# Pratica_02.net
KiCad netlist of a schematic drawn in EasyEDA
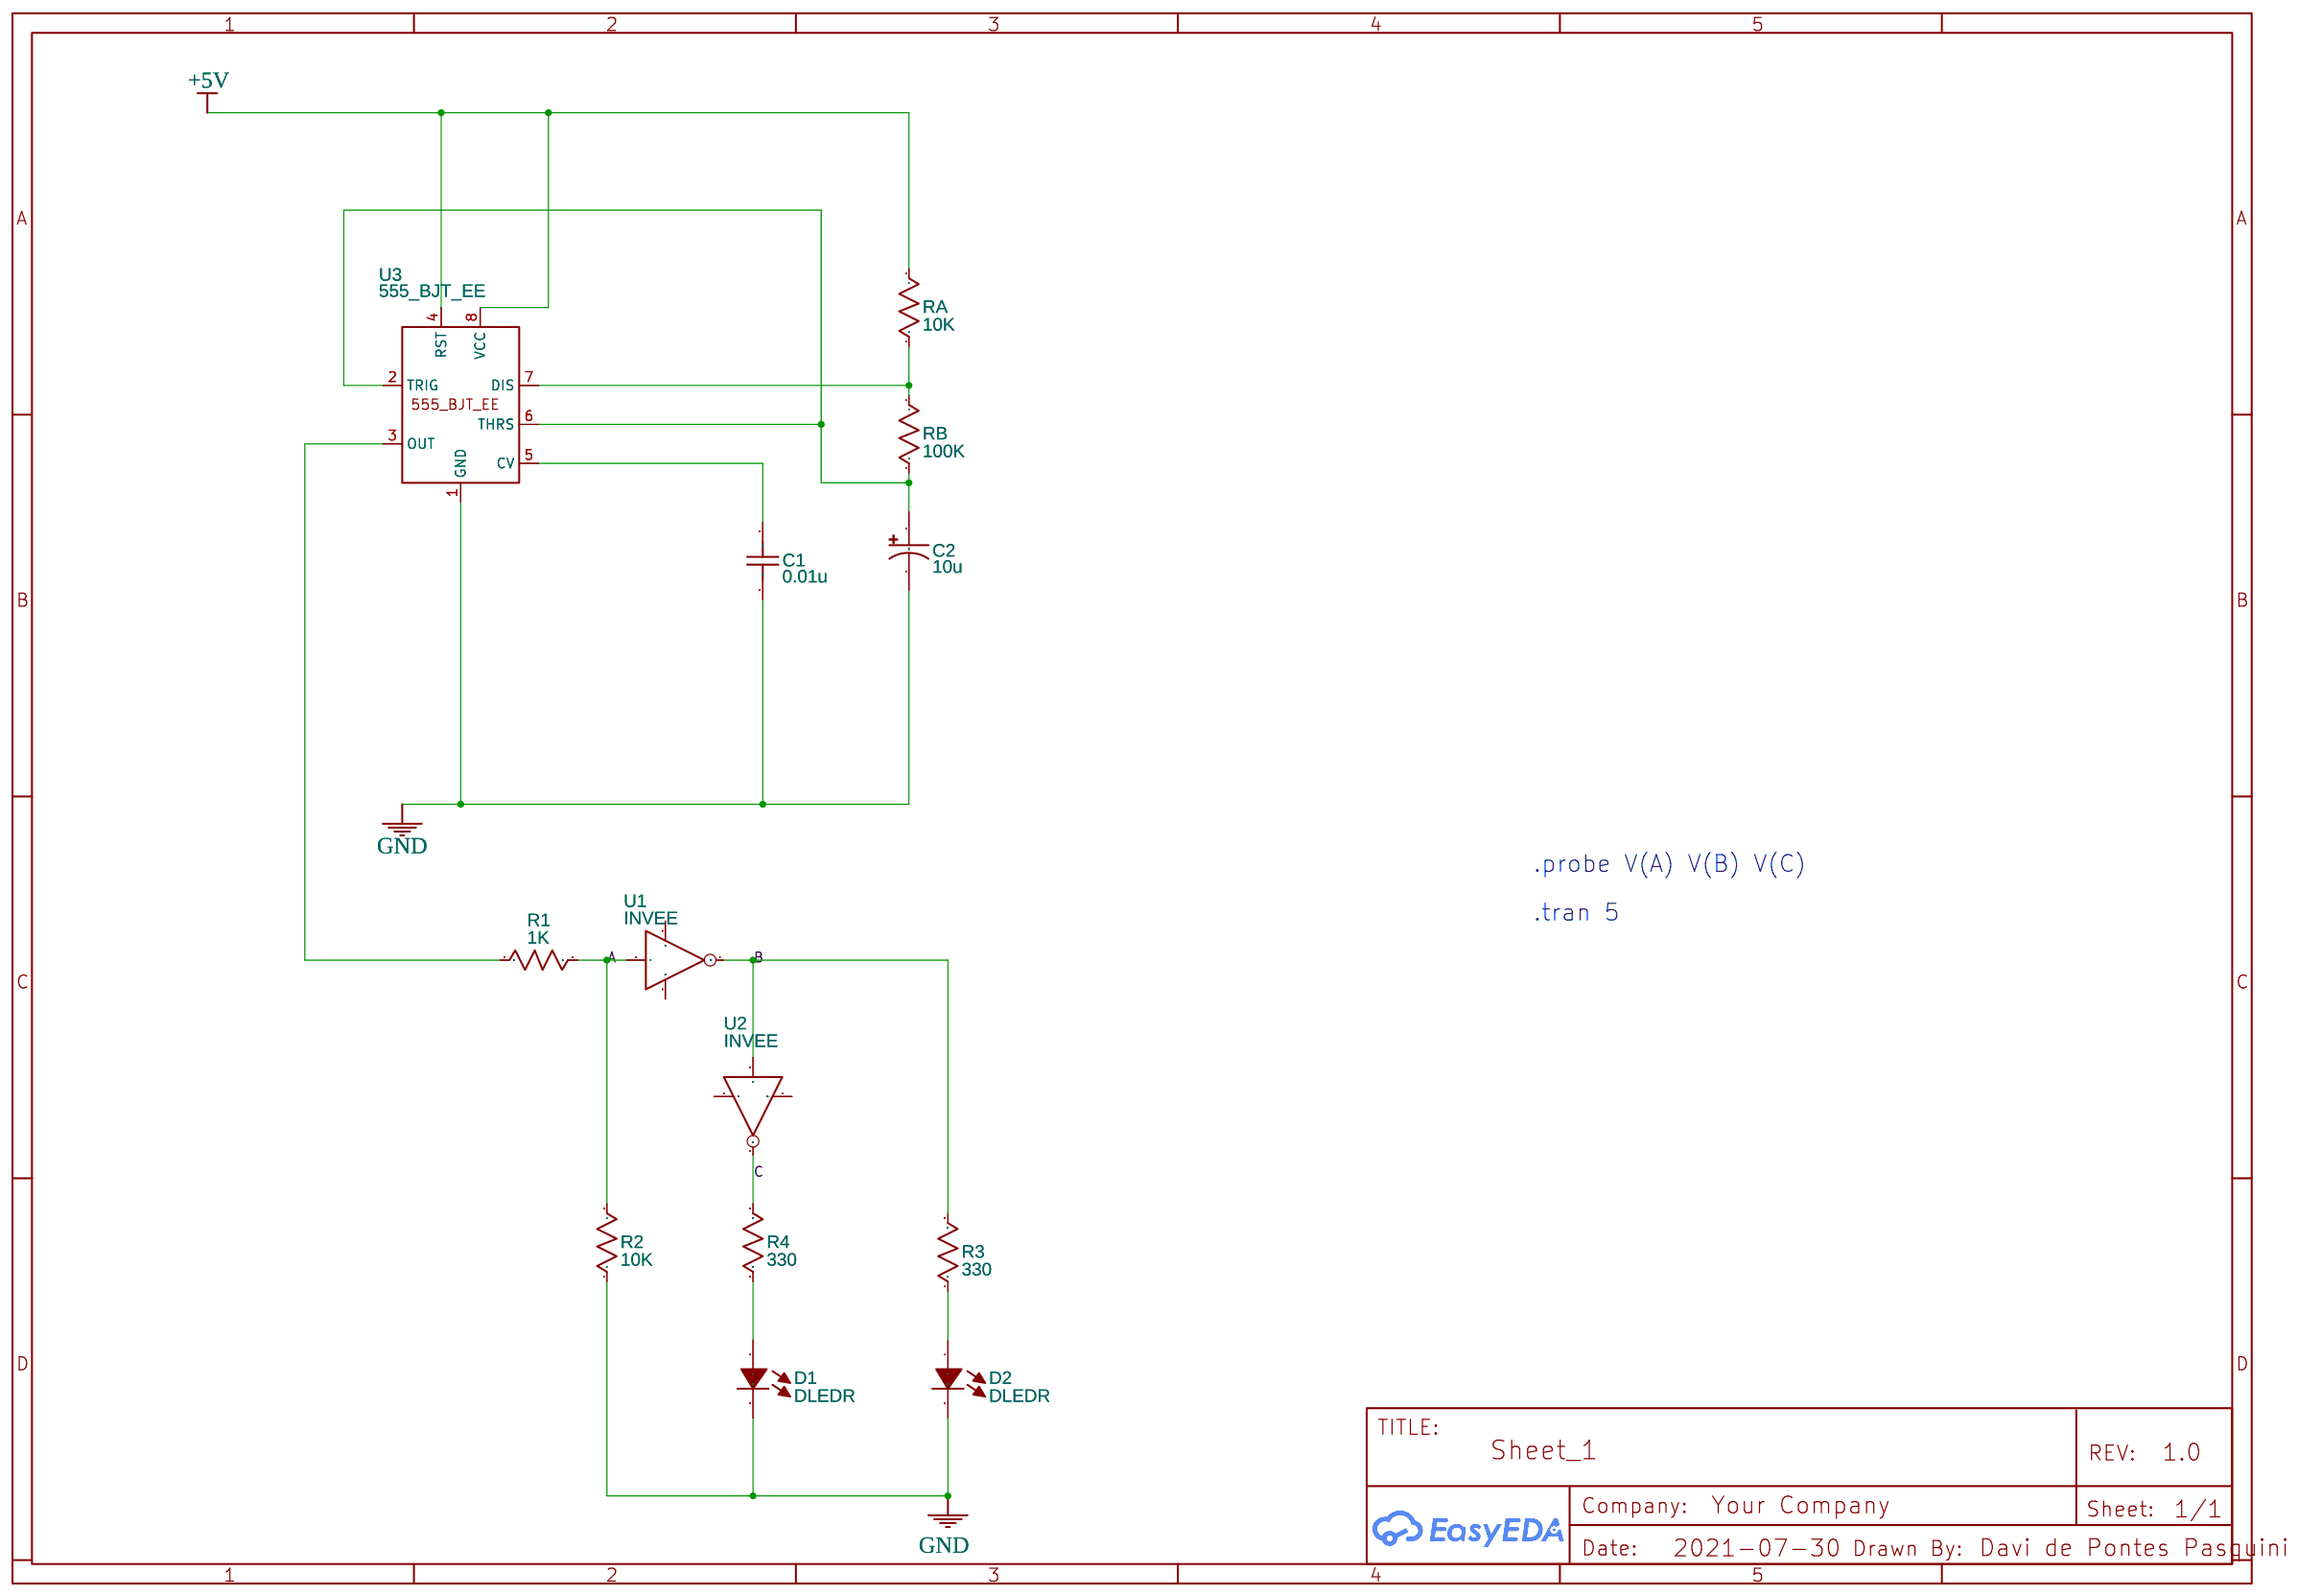
[diagram p0: schematic sheet]

(export (version "E")
  (design (tool "Eeschema 10.0.6"))
  (components
    (comp (ref "C1") (value "0.01u") (libsource (lib "") (part "Capacitor_US")))
    (comp (ref "C2") (value "10u") (libsource (lib "") (part "Capacitor_Electrolytic_US")))
    (comp (ref "D1") (value "DLEDR") (libsource (lib "") (part "DLEDR")))
    (comp (ref "D2") (value "DLEDR") (libsource (lib "") (part "DLEDR")))
    (comp (ref "R1") (value "1K") (libsource (lib "") (part "Resistor_US_1")))
    (comp (ref "R2") (value "10K") (libsource (lib "") (part "Resistor_US_2")))
    (comp (ref "R3") (value "330") (libsource (lib "") (part "Resistor_US_2")))
    (comp (ref "R4") (value "330") (libsource (lib "") (part "Resistor_US_2")))
    (comp (ref "RA") (value "10K") (libsource (lib "") (part "Resistor_US_3")))
    (comp (ref "RB") (value "100K") (libsource (lib "") (part "Resistor_US")))
    (comp (ref "U1") (value "INVEE") (libsource (lib "") (part "LOGIC")))
    (comp (ref "U2") (value "INVEE") (libsource (lib "") (part "LOGIC_1")))
    (comp (ref "U3") (value "555_BJT_EE") (libsource (lib "") (part "555_BJT_EE")))
  )
  (nets
    (net (code "1") (name "+5V") (class "Default")
      (node (ref "RA") (pin "1") (pinfunction "1_1") (pintype "unspecified"))
      (node (ref "U3") (pin "4") (pinfunction "RST_4") (pintype "unspecified"))
      (node (ref "U3") (pin "8") (pinfunction "VCC_8") (pintype "unspecified"))
    )
    (net (code "2") (name "/A") (class "Default")
      (node (ref "R1") (pin "2") (pinfunction "2_2") (pintype "unspecified"))
      (node (ref "R2") (pin "2") (pinfunction "2_2") (pintype "unspecified"))
      (node (ref "U1") (pin "1") (pinfunction "IN_1") (pintype "input"))
    )
    (net (code "3") (name "/B") (class "Default")
      (node (ref "R3") (pin "2") (pinfunction "2_2") (pintype "unspecified"))
      (node (ref "U1") (pin "4") (pinfunction "OUT_4") (pintype "output"))
      (node (ref "U2") (pin "1") (pinfunction "IN_1") (pintype "input"))
    )
    (net (code "4") (name "/C") (class "Default")
      (node (ref "R4") (pin "2") (pinfunction "2_2") (pintype "unspecified"))
      (node (ref "U2") (pin "4") (pinfunction "OUT_4") (pintype "output"))
    )
    (net (code "5") (name "GND") (class "Default")
      (node (ref "C1") (pin "1") (pinfunction "1_1") (pintype "unspecified"))
      (node (ref "C2") (pin "2") (pinfunction "2_2") (pintype "unspecified"))
      (node (ref "D1") (pin "2") (pinfunction "C_2") (pintype "unspecified"))
      (node (ref "D2") (pin "2") (pinfunction "C_2") (pintype "unspecified"))
      (node (ref "R2") (pin "1") (pinfunction "1_1") (pintype "unspecified"))
      (node (ref "U3") (pin "1") (pinfunction "GND_1") (pintype "unspecified"))
    )
    (net (code "6") (name "Net-(D1-A)") (class "Default")
      (node (ref "D1") (pin "1") (pinfunction "A_1") (pintype "unspecified"))
      (node (ref "R4") (pin "1") (pinfunction "1_1") (pintype "unspecified"))
    )
    (net (code "7") (name "Net-(D2-A)") (class "Default")
      (node (ref "D2") (pin "1") (pinfunction "A_1") (pintype "unspecified"))
      (node (ref "R3") (pin "1") (pinfunction "1_1") (pintype "unspecified"))
    )
    (net (code "8") (name "Net-(U3-CV)") (class "Default")
      (node (ref "C1") (pin "2") (pinfunction "2_2") (pintype "unspecified"))
      (node (ref "U3") (pin "5") (pinfunction "CV_5") (pintype "unspecified"))
    )
    (net (code "9") (name "Net-(U3-DIS)") (class "Default")
      (node (ref "RA") (pin "2") (pinfunction "2_2") (pintype "unspecified"))
      (node (ref "RB") (pin "1") (pinfunction "1_1") (pintype "unspecified"))
      (node (ref "U3") (pin "7") (pinfunction "DIS_7") (pintype "unspecified"))
    )
    (net (code "10") (name "Net-(U3-OUT)") (class "Default")
      (node (ref "R1") (pin "1") (pinfunction "1_1") (pintype "unspecified"))
      (node (ref "U3") (pin "3") (pinfunction "OUT_3") (pintype "unspecified"))
    )
    (net (code "11") (name "Net-(U3-THRS)") (class "Default")
      (node (ref "C2") (pin "1") (pinfunction "1_1") (pintype "unspecified"))
      (node (ref "RB") (pin "2") (pinfunction "2_2") (pintype "unspecified"))
      (node (ref "U3") (pin "2") (pinfunction "TRIG_2") (pintype "unspecified"))
      (node (ref "U3") (pin "6") (pinfunction "THRS_6") (pintype "unspecified"))
    )
    (net (code "12") (name "unconnected-(U1-GND-Pad3)") (class "Default")
      (node (ref "U1") (pin "3") (pinfunction "GND_3") (pintype "passive"))
    )
    (net (code "13") (name "unconnected-(U1-VDD-Pad2)") (class "Default")
      (node (ref "U1") (pin "2") (pinfunction "VDD_2") (pintype "passive"))
    )
    (net (code "14") (name "unconnected-(U2-GND-Pad3)") (class "Default")
      (node (ref "U2") (pin "3") (pinfunction "GND_3") (pintype "passive"))
    )
    (net (code "15") (name "unconnected-(U2-VDD-Pad2)") (class "Default")
      (node (ref "U2") (pin "2") (pinfunction "VDD_2") (pintype "passive"))
    )
  )
)
